# MicroMultimeter__PROBE_Sch.net
KiCad netlist of a schematic drawn in Altium Designer
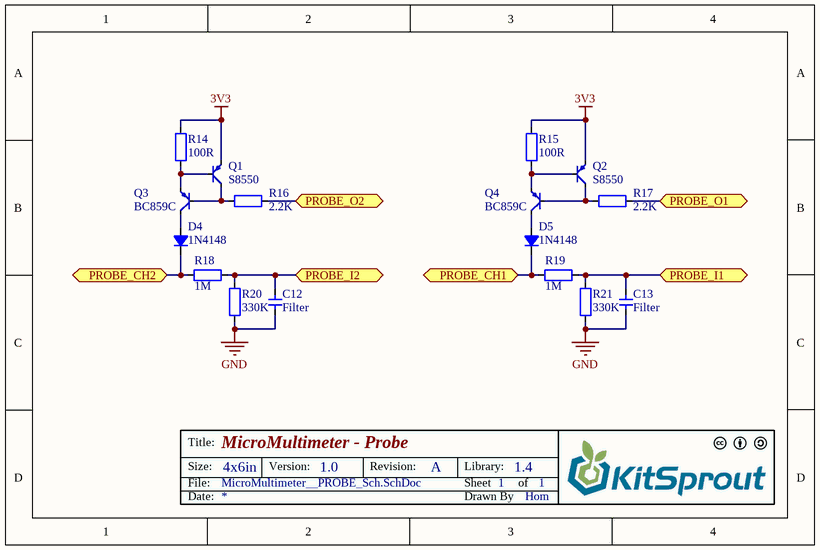
[diagram p0: MicroMultimeter__PROBE_Sch.SchDoc]

(export (version "E")
  (design (tool "Eeschema 10.0.6"))
  (components
    (comp (ref "C12")
      (value "Filter")
      (footprint "PCB_PassiveCap:CAP_0603")
      (description "Capacitor")
      (fields (field (name "Comment") "Cap_0603"))
      (libsource (lib "SCH_Passive") (part "Cap_0603"))
    )
    (comp (ref "C13")
      (value "Filter")
      (footprint "PCB_PassiveCap:CAP_0603")
      (description "Capacitor")
      (fields (field (name "Comment") "Cap_0603"))
      (libsource (lib "SCH_Passive") (part "Cap_0603"))
    )
    (comp (ref "D4")
      (value "1N4148")
      (footprint "PCB_ActiveDIO:SOD323")
      (description "Diode")
      (fields (field (name "Comment") "Diode_SOD323"))
      (libsource (lib "SCH_Active") (part "Diode_SOD323"))
    )
    (comp (ref "D5")
      (value "1N4148")
      (footprint "PCB_ActiveDIO:SOD323")
      (description "Diode")
      (fields (field (name "Comment") "Diode_SOD323"))
      (libsource (lib "SCH_Active") (part "Diode_SOD323"))
    )
    (comp (ref "Q1")
      (value "S8550")
      (footprint "PCB_IntegratedCircuit:SOT23-3")
      (description "Transistor")
      (fields (field (name "Comment") "BJT_PNP"))
      (libsource (lib "SCH_Active") (part "BJT_PNP"))
    )
    (comp (ref "Q2")
      (value "S8550")
      (footprint "PCB_IntegratedCircuit:SOT23-3")
      (description "Transistor")
      (fields (field (name "Comment") "BJT_PNP"))
      (libsource (lib "SCH_Active") (part "BJT_PNP"))
    )
    (comp (ref "Q3")
      (value "BC859C")
      (footprint "PCB_IntegratedCircuit:SOT23-3")
      (description "Transistor")
      (fields (field (name "Comment") "BJT_PNP"))
      (libsource (lib "SCH_Active") (part "BJT_PNP"))
    )
    (comp (ref "Q4")
      (value "BC859C")
      (footprint "PCB_IntegratedCircuit:SOT23-3")
      (description "Transistor")
      (fields (field (name "Comment") "BJT_PNP"))
      (libsource (lib "SCH_Active") (part "BJT_PNP"))
    )
    (comp (ref "R14")
      (value "100R")
      (footprint "PCB_PassiveRes:RES_0603")
      (description "Resistor")
      (fields (field (name "Comment") "Res_0603"))
      (libsource (lib "") (part "Res_0603_1"))
    )
    (comp (ref "R15")
      (value "100R")
      (footprint "PCB_PassiveRes:RES_0603")
      (description "Resistor")
      (fields (field (name "Comment") "Res_0603"))
      (libsource (lib "") (part "Res_0603_1"))
    )
    (comp (ref "R16")
      (value "2.2K")
      (footprint "PCB_PassiveRes:RES_0603")
      (description "Resistor")
      (fields (field (name "Comment") "Res_0603"))
      (libsource (lib "SCH_Passive") (part "Res_0603"))
    )
    (comp (ref "R17")
      (value "2.2K")
      (footprint "PCB_PassiveRes:RES_0603")
      (description "Resistor")
      (fields (field (name "Comment") "Res_0603"))
      (libsource (lib "SCH_Passive") (part "Res_0603"))
    )
    (comp (ref "R18")
      (value "1M")
      (footprint "PCB_PassiveRes:RES_0603")
      (description "Resistor")
      (fields (field (name "Comment") "Res_0603"))
      (libsource (lib "SCH_Passive") (part "Res_0603"))
    )
    (comp (ref "R19")
      (value "1M")
      (footprint "PCB_PassiveRes:RES_0603")
      (description "Resistor")
      (fields (field (name "Comment") "Res_0603"))
      (libsource (lib "SCH_Passive") (part "Res_0603"))
    )
    (comp (ref "R20")
      (value "330K")
      (footprint "PCB_PassiveRes:RES_0603")
      (description "Resistor")
      (fields (field (name "Comment") "Res_0603"))
      (libsource (lib "") (part "Res_0603_1"))
    )
    (comp (ref "R21")
      (value "330K")
      (footprint "PCB_PassiveRes:RES_0603")
      (description "Resistor")
      (fields (field (name "Comment") "Res_0603"))
      (libsource (lib "") (part "Res_0603_1"))
    )
  )
  (nets
    (net (code "1") (name "/PROBE_CH1") (class "Default")
      (node (ref "D5") (pin "2") (pinfunction "K_2") (pintype "passive"))
      (node (ref "R19") (pin "2") (pinfunction "2_2") (pintype "passive"))
    )
    (net (code "2") (name "/PROBE_CH2") (class "Default")
      (node (ref "D4") (pin "2") (pinfunction "K_2") (pintype "passive"))
      (node (ref "R18") (pin "2") (pinfunction "2_2") (pintype "passive"))
    )
    (net (code "3") (name "/PROBE_I1") (class "Default")
      (node (ref "C13") (pin "2") (pinfunction "2_2") (pintype "passive"))
      (node (ref "R19") (pin "1") (pinfunction "1_1") (pintype "passive"))
      (node (ref "R21") (pin "2") (pinfunction "2_2") (pintype "passive"))
    )
    (net (code "4") (name "/PROBE_I2") (class "Default")
      (node (ref "C12") (pin "2") (pinfunction "2_2") (pintype "passive"))
      (node (ref "R18") (pin "1") (pinfunction "1_1") (pintype "passive"))
      (node (ref "R20") (pin "2") (pinfunction "2_2") (pintype "passive"))
    )
    (net (code "5") (name "/PROBE_O1") (class "Default")
      (node (ref "R17") (pin "1") (pinfunction "1_1") (pintype "passive"))
    )
    (net (code "6") (name "/PROBE_O2") (class "Default")
      (node (ref "R16") (pin "1") (pinfunction "1_1") (pintype "passive"))
    )
    (net (code "7") (name "3V3") (class "Default")
      (node (ref "Q1") (pin "2") (pinfunction "E_2") (pintype "passive"))
      (node (ref "Q2") (pin "2") (pinfunction "E_2") (pintype "passive"))
      (node (ref "R14") (pin "2") (pinfunction "2_2") (pintype "passive"))
      (node (ref "R15") (pin "2") (pinfunction "2_2") (pintype "passive"))
    )
    (net (code "8") (name "GND") (class "Default")
      (node (ref "C12") (pin "1") (pinfunction "1_1") (pintype "passive"))
      (node (ref "C13") (pin "1") (pinfunction "1_1") (pintype "passive"))
      (node (ref "R20") (pin "1") (pinfunction "1_1") (pintype "passive"))
      (node (ref "R21") (pin "1") (pinfunction "1_1") (pintype "passive"))
    )
    (net (code "9") (name "Net-(D4-A)") (class "Default")
      (node (ref "D4") (pin "1") (pinfunction "A_1") (pintype "passive"))
      (node (ref "Q3") (pin "3") (pinfunction "C_3") (pintype "passive"))
    )
    (net (code "10") (name "Net-(D5-A)") (class "Default")
      (node (ref "D5") (pin "1") (pinfunction "A_1") (pintype "passive"))
      (node (ref "Q4") (pin "3") (pinfunction "C_3") (pintype "passive"))
    )
    (net (code "11") (name "Net-(Q1-B)") (class "Default")
      (node (ref "Q1") (pin "1") (pinfunction "B_1") (pintype "passive"))
      (node (ref "Q3") (pin "2") (pinfunction "E_2") (pintype "passive"))
      (node (ref "R14") (pin "1") (pinfunction "1_1") (pintype "passive"))
    )
    (net (code "12") (name "Net-(Q1-C)") (class "Default")
      (node (ref "Q1") (pin "3") (pinfunction "C_3") (pintype "passive"))
      (node (ref "Q3") (pin "1") (pinfunction "B_1") (pintype "passive"))
      (node (ref "R16") (pin "2") (pinfunction "2_2") (pintype "passive"))
    )
    (net (code "13") (name "Net-(Q2-B)") (class "Default")
      (node (ref "Q2") (pin "1") (pinfunction "B_1") (pintype "passive"))
      (node (ref "Q4") (pin "2") (pinfunction "E_2") (pintype "passive"))
      (node (ref "R15") (pin "1") (pinfunction "1_1") (pintype "passive"))
    )
    (net (code "14") (name "Net-(Q2-C)") (class "Default")
      (node (ref "Q2") (pin "3") (pinfunction "C_3") (pintype "passive"))
      (node (ref "Q4") (pin "1") (pinfunction "B_1") (pintype "passive"))
      (node (ref "R17") (pin "2") (pinfunction "2_2") (pintype "passive"))
    )
  )
)
